# ADC.net
KiCad netlist of a schematic drawn in Altium Designer
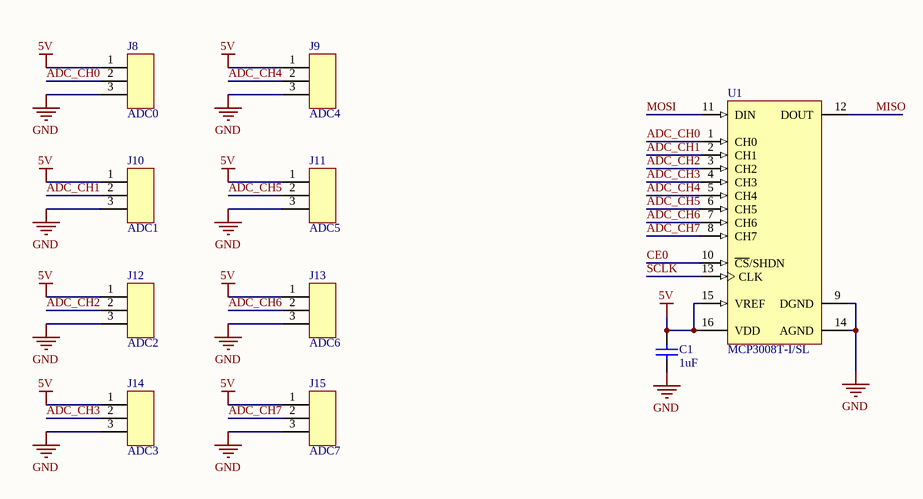
[diagram p0: ADC.SchDoc]

(export (version "E")
  (design (tool "Eeschema 10.0.6"))
  (components
    (comp (ref "C1")
      (value "1uF")
      (footprint "C0805")
      (description "0805 1 uF 25 V ±10 % Tolerance X7R SMT Multilayer Ceramic Capacitor")
      (fields (field (name "MANUFACTURER PART NUMBER") "CC0805KKX7R8BB105"))
      (libsource (lib "CommunityVault") (part "CMP-77c3bc4dc880a804-3"))
    )
    (comp (ref "J8")
      (value "ADC0")
      (footprint "PCB-s0hfil65plaomi4ibvcw-1")
      (description "THT Vertical Pin Header WR-PHD, Pitch 2.54 mm, Single Row, 3 pins")
      (fields (field (name "MANUFACTURER PART NUMBER") "61300311121"))
      (libsource (lib "CommunityVault") (part "SYM-8a90426ffa175557-17"))
    )
    (comp (ref "J9")
      (value "ADC4")
      (footprint "PCB-s0hfil65plaomi4ibvcw-1")
      (description "THT Vertical Pin Header WR-PHD, Pitch 2.54 mm, Single Row, 3 pins")
      (fields (field (name "MANUFACTURER PART NUMBER") "61300311121"))
      (libsource (lib "CommunityVault") (part "SYM-8a90426ffa175557-17"))
    )
    (comp (ref "J10")
      (value "ADC1")
      (footprint "PCB-s0hfil65plaomi4ibvcw-1")
      (description "THT Vertical Pin Header WR-PHD, Pitch 2.54 mm, Single Row, 3 pins")
      (fields (field (name "MANUFACTURER PART NUMBER") "61300311121"))
      (libsource (lib "CommunityVault") (part "SYM-8a90426ffa175557-17"))
    )
    (comp (ref "J11")
      (value "ADC5")
      (footprint "PCB-s0hfil65plaomi4ibvcw-1")
      (description "THT Vertical Pin Header WR-PHD, Pitch 2.54 mm, Single Row, 3 pins")
      (fields (field (name "MANUFACTURER PART NUMBER") "61300311121"))
      (libsource (lib "CommunityVault") (part "SYM-8a90426ffa175557-17"))
    )
    (comp (ref "J12")
      (value "ADC2")
      (footprint "PCB-s0hfil65plaomi4ibvcw-1")
      (description "THT Vertical Pin Header WR-PHD, Pitch 2.54 mm, Single Row, 3 pins")
      (fields (field (name "MANUFACTURER PART NUMBER") "61300311121"))
      (libsource (lib "CommunityVault") (part "SYM-8a90426ffa175557-17"))
    )
    (comp (ref "J13")
      (value "ADC6")
      (footprint "PCB-s0hfil65plaomi4ibvcw-1")
      (description "THT Vertical Pin Header WR-PHD, Pitch 2.54 mm, Single Row, 3 pins")
      (fields (field (name "MANUFACTURER PART NUMBER") "61300311121"))
      (libsource (lib "CommunityVault") (part "SYM-8a90426ffa175557-17"))
    )
    (comp (ref "J14")
      (value "ADC3")
      (footprint "PCB-s0hfil65plaomi4ibvcw-1")
      (description "THT Vertical Pin Header WR-PHD, Pitch 2.54 mm, Single Row, 3 pins")
      (fields (field (name "MANUFACTURER PART NUMBER") "61300311121"))
      (libsource (lib "CommunityVault") (part "SYM-8a90426ffa175557-17"))
    )
    (comp (ref "J15")
      (value "ADC7")
      (footprint "PCB-s0hfil65plaomi4ibvcw-1")
      (description "THT Vertical Pin Header WR-PHD, Pitch 2.54 mm, Single Row, 3 pins")
      (fields (field (name "MANUFACTURER PART NUMBER") "61300311121"))
      (libsource (lib "CommunityVault") (part "SYM-8a90426ffa175557-17"))
    )
    (comp (ref "U1")
      (value "MCP3008T-I/SL")
      (footprint "SOIC-SL16_L")
      (libsource (lib "CommunityVault") (part "CON-ADC-MCP3008-16"))
    )
  )
  (nets
    (net (code "1") (name "/ADC_CH0") (class "Default")
      (node (ref "J8") (pin "2") (pinfunction "2_2") (pintype "passive"))
      (node (ref "U1") (pin "1") (pinfunction "CH0_1") (pintype "input"))
    )
    (net (code "2") (name "/ADC_CH1") (class "Default")
      (node (ref "J10") (pin "2") (pinfunction "2_2") (pintype "passive"))
      (node (ref "U1") (pin "2") (pinfunction "CH1_2") (pintype "input"))
    )
    (net (code "3") (name "/ADC_CH2") (class "Default")
      (node (ref "J12") (pin "2") (pinfunction "2_2") (pintype "passive"))
      (node (ref "U1") (pin "3") (pinfunction "CH2_3") (pintype "input"))
    )
    (net (code "4") (name "/ADC_CH3") (class "Default")
      (node (ref "J14") (pin "2") (pinfunction "2_2") (pintype "passive"))
      (node (ref "U1") (pin "4") (pinfunction "CH3_4") (pintype "input"))
    )
    (net (code "5") (name "/ADC_CH4") (class "Default")
      (node (ref "J9") (pin "2") (pinfunction "2_2") (pintype "passive"))
      (node (ref "U1") (pin "5") (pinfunction "CH4_5") (pintype "input"))
    )
    (net (code "6") (name "/ADC_CH5") (class "Default")
      (node (ref "J11") (pin "2") (pinfunction "2_2") (pintype "passive"))
      (node (ref "U1") (pin "6") (pinfunction "CH5_6") (pintype "input"))
    )
    (net (code "7") (name "/ADC_CH6") (class "Default")
      (node (ref "J13") (pin "2") (pinfunction "2_2") (pintype "passive"))
      (node (ref "U1") (pin "7") (pinfunction "CH6_7") (pintype "input"))
    )
    (net (code "8") (name "/ADC_CH7") (class "Default")
      (node (ref "J15") (pin "2") (pinfunction "2_2") (pintype "passive"))
      (node (ref "U1") (pin "8") (pinfunction "CH7_8") (pintype "input"))
    )
    (net (code "9") (name "/CE0") (class "Default")
      (node (ref "U1") (pin "10") (pinfunction "~{CS}/SHDN_10") (pintype "input"))
    )
    (net (code "10") (name "/MISO") (class "Default")
      (node (ref "U1") (pin "12") (pinfunction "DOUT_12") (pintype "tri_state"))
    )
    (net (code "11") (name "/MOSI") (class "Default")
      (node (ref "U1") (pin "11") (pinfunction "DIN_11") (pintype "input"))
    )
    (net (code "12") (name "/SCLK") (class "Default")
      (node (ref "U1") (pin "13") (pinfunction "CLK_13") (pintype "input"))
    )
    (net (code "13") (name "5V") (class "Default")
      (node (ref "C1") (pin "1") (pinfunction "1_1") (pintype "passive"))
      (node (ref "J10") (pin "1") (pinfunction "1_1") (pintype "passive"))
      (node (ref "J11") (pin "1") (pinfunction "1_1") (pintype "passive"))
      (node (ref "J12") (pin "1") (pinfunction "1_1") (pintype "passive"))
      (node (ref "J13") (pin "1") (pinfunction "1_1") (pintype "passive"))
      (node (ref "J14") (pin "1") (pinfunction "1_1") (pintype "passive"))
      (node (ref "J15") (pin "1") (pinfunction "1_1") (pintype "passive"))
      (node (ref "J8") (pin "1") (pinfunction "1_1") (pintype "passive"))
      (node (ref "J9") (pin "1") (pinfunction "1_1") (pintype "passive"))
      (node (ref "U1") (pin "15") (pinfunction "VREF_15") (pintype "input"))
      (node (ref "U1") (pin "16") (pinfunction "VDD_16") (pintype "power_in"))
    )
    (net (code "14") (name "GND") (class "Default")
      (node (ref "C1") (pin "2") (pinfunction "2_2") (pintype "passive"))
      (node (ref "J10") (pin "3") (pinfunction "3_3") (pintype "passive"))
      (node (ref "J11") (pin "3") (pinfunction "3_3") (pintype "passive"))
      (node (ref "J12") (pin "3") (pinfunction "3_3") (pintype "passive"))
      (node (ref "J13") (pin "3") (pinfunction "3_3") (pintype "passive"))
      (node (ref "J14") (pin "3") (pinfunction "3_3") (pintype "passive"))
      (node (ref "J15") (pin "3") (pinfunction "3_3") (pintype "passive"))
      (node (ref "J8") (pin "3") (pinfunction "3_3") (pintype "passive"))
      (node (ref "J9") (pin "3") (pinfunction "3_3") (pintype "passive"))
      (node (ref "U1") (pin "14") (pinfunction "AGND_14") (pintype "power_in"))
      (node (ref "U1") (pin "9") (pinfunction "DGND_9") (pintype "power_in"))
    )
  )
)
